# 3_RFID.net
KiCad netlist of a schematic drawn in Altium Designer
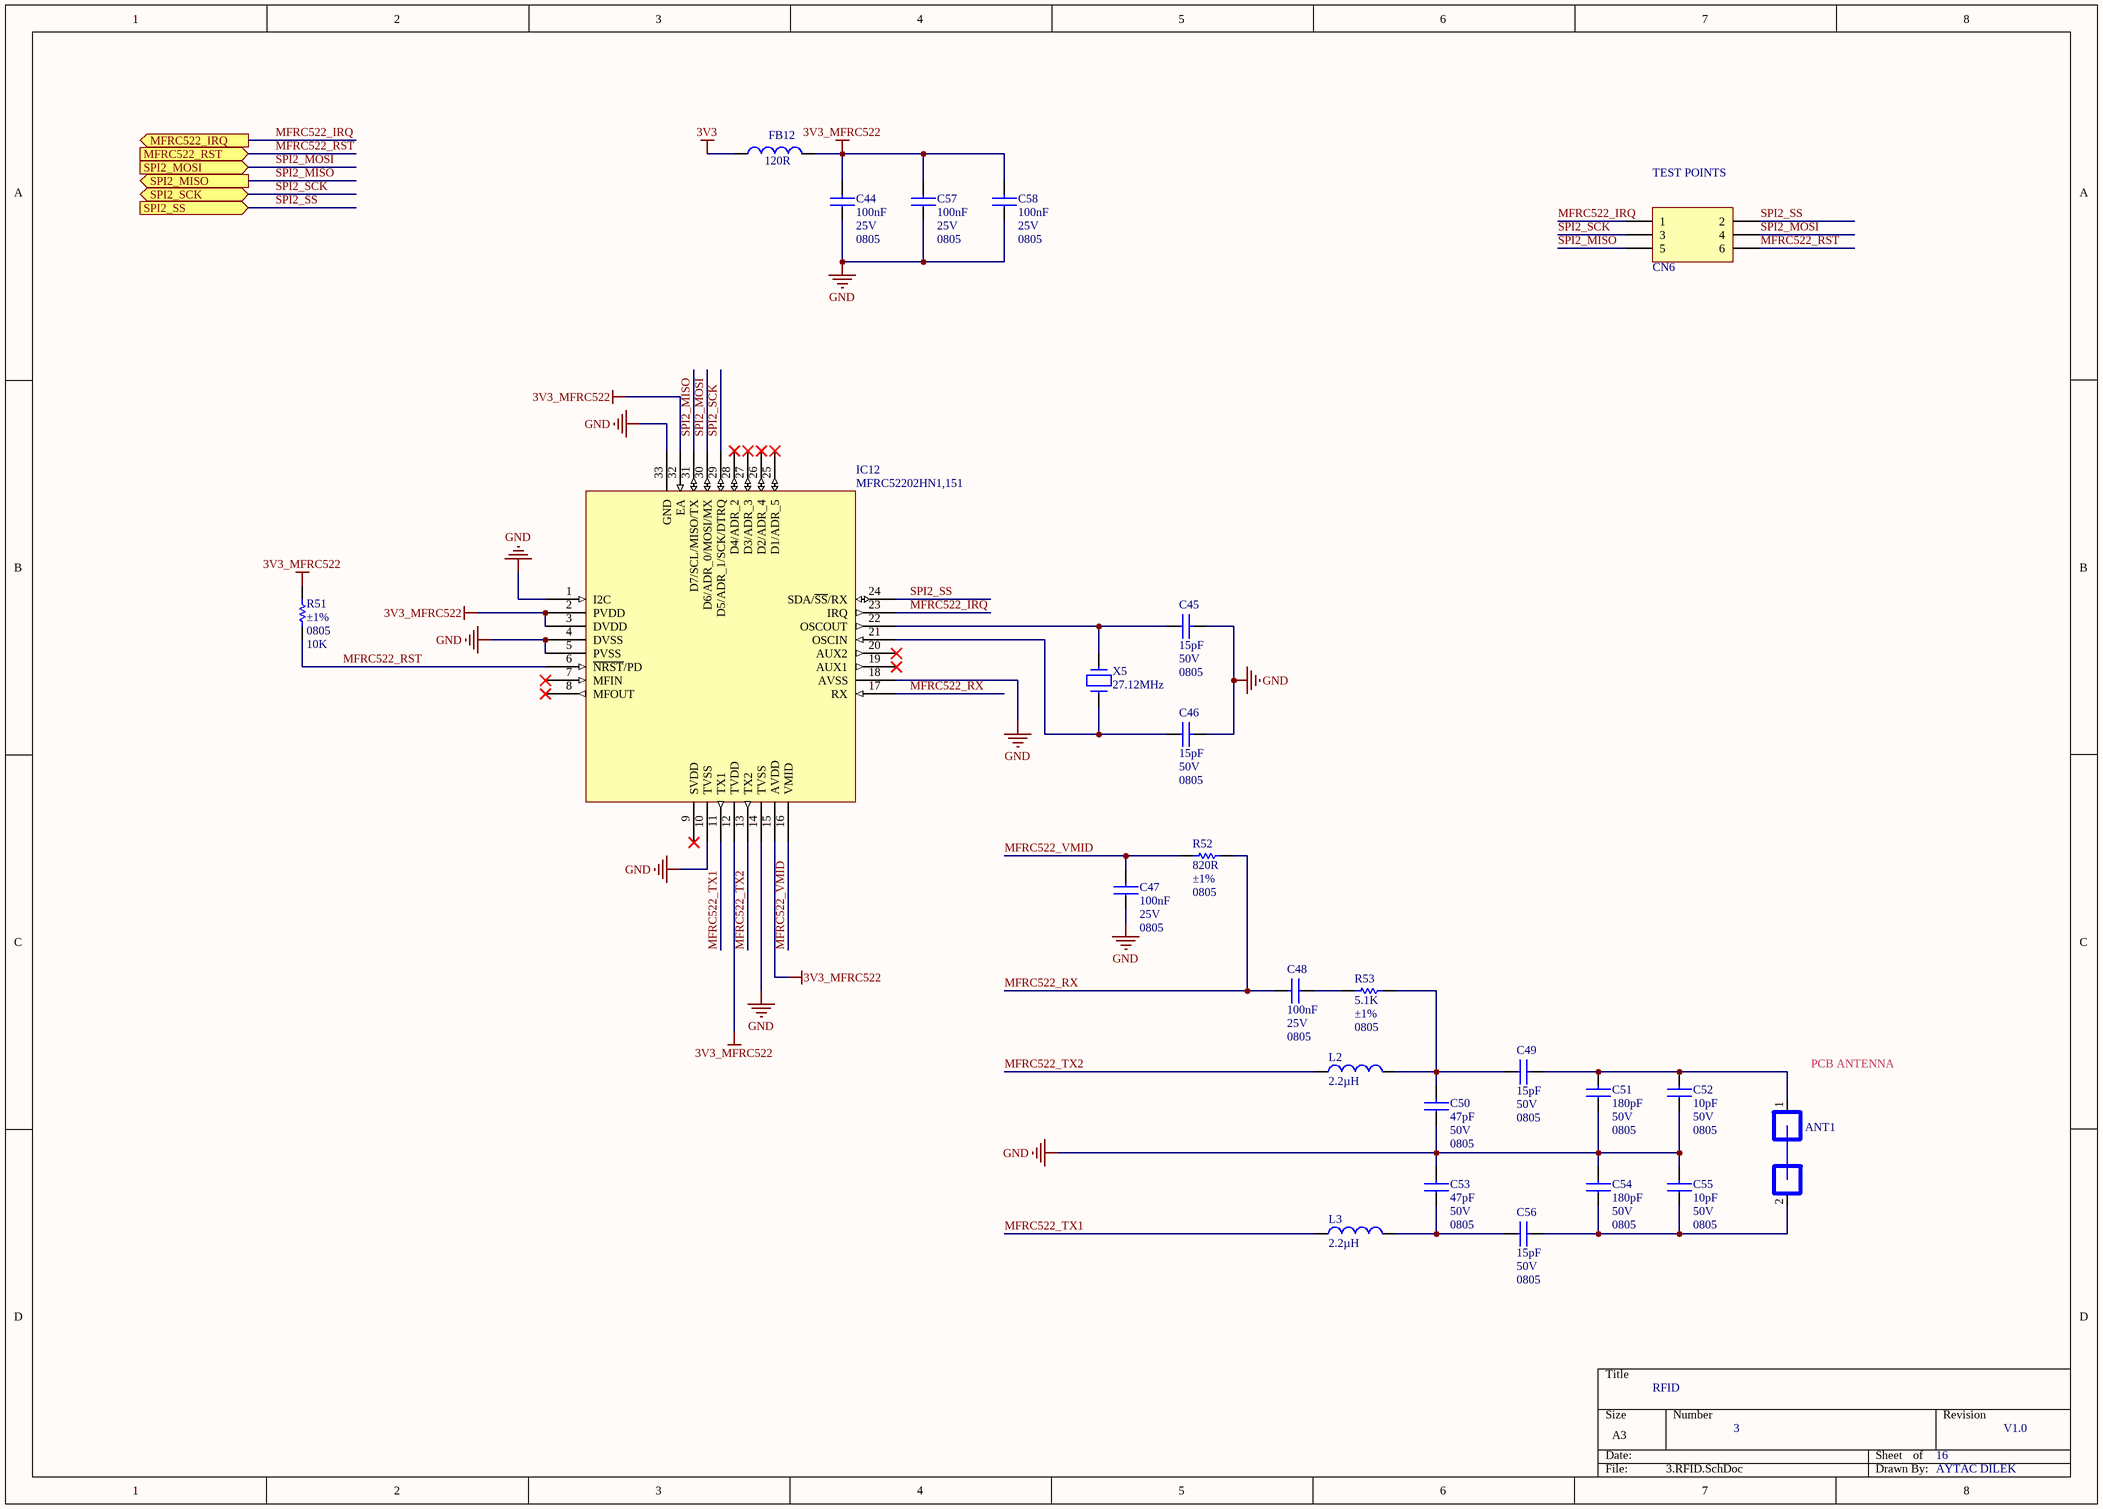
[diagram p0: 3.RFID.SchDoc]

(export (version "E")
  (design (tool "Eeschema 10.0.6"))
  (components
    (comp (ref "ANT1")
      (value "COIL_ANTENNA_PAD")
      (footprint "COIL_ANTENNA_PAD")
      (description "Coil Antenna Pad")
      (fields (field (name "PART NUMBER") "SMSC00008"))
      (libsource (lib "ComponentDatabase") (part "COIL_ANTENNA_PAD"))
    )
    (comp (ref "C44")
      (value "CAP_NP")
      (footprint "CAPC2012X100N_EIA0805")
      (description "CAP CER 0.1UF 25V X7R 0805")
      (fields
        (field (name "PART NUMBER") "SCAP00300093")
        (field (name "CAPACITANCE") "100nF")
        (field (name "TOLERANCE") "±10%")
        (field (name "VOLTAGE - RATED") "25V")
        (field (name "PACKAGE / CASE") "0805")
      )
      (libsource (lib "ComponentDatabase") (part "CAP_NP"))
    )
    (comp (ref "C45")
      (value "CAP_NP")
      (footprint "CAPC2012X100N_EIA0805")
      (description "CAP CER 15PF 50V NP0 0805")
      (fields
        (field (name "PART NUMBER") "SCAP00300038")
        (field (name "CAPACITANCE") "15pF")
        (field (name "TOLERANCE") "±5%")
        (field (name "VOLTAGE - RATED") "50V")
        (field (name "PACKAGE / CASE") "0805")
      )
      (libsource (lib "ComponentDatabase") (part "CAP_NP"))
    )
    (comp (ref "C46")
      (value "CAP_NP")
      (footprint "CAPC2012X100N_EIA0805")
      (description "CAP CER 15PF 50V NP0 0805")
      (fields
        (field (name "PART NUMBER") "SCAP00300038")
        (field (name "CAPACITANCE") "15pF")
        (field (name "TOLERANCE") "±5%")
        (field (name "VOLTAGE - RATED") "50V")
        (field (name "PACKAGE / CASE") "0805")
      )
      (libsource (lib "ComponentDatabase") (part "CAP_NP"))
    )
    (comp (ref "C47")
      (value "CAP_NP")
      (footprint "CAPC2012X100N_EIA0805")
      (description "CAP CER 0.1UF 25V X7R 0805")
      (fields
        (field (name "PART NUMBER") "SCAP00300093")
        (field (name "CAPACITANCE") "100nF")
        (field (name "TOLERANCE") "±10%")
        (field (name "VOLTAGE - RATED") "25V")
        (field (name "PACKAGE / CASE") "0805")
      )
      (libsource (lib "ComponentDatabase") (part "CAP_NP"))
    )
    (comp (ref "C48")
      (value "CAP_NP")
      (footprint "CAPC2012X100N_EIA0805")
      (description "CAP CER 0.1UF 25V X7R 0805")
      (fields
        (field (name "PART NUMBER") "SCAP00300093")
        (field (name "CAPACITANCE") "100nF")
        (field (name "TOLERANCE") "±10%")
        (field (name "VOLTAGE - RATED") "25V")
        (field (name "PACKAGE / CASE") "0805")
      )
      (libsource (lib "ComponentDatabase") (part "CAP_NP"))
    )
    (comp (ref "C49")
      (value "CAP_NP")
      (footprint "CAPC2012X100N_EIA0805")
      (description "CAP CER 15PF 50V NP0 0805")
      (fields
        (field (name "PART NUMBER") "SCAP00300038")
        (field (name "CAPACITANCE") "15pF")
        (field (name "TOLERANCE") "±5%")
        (field (name "VOLTAGE - RATED") "50V")
        (field (name "PACKAGE / CASE") "0805")
      )
      (libsource (lib "ComponentDatabase") (part "CAP_NP"))
    )
    (comp (ref "C50")
      (value "CAP_NP")
      (footprint "CAPC2012X100N_EIA0805")
      (description "CAP CER 47PF 50V NP0 0805")
      (fields
        (field (name "PART NUMBER") "SCAP00300050")
        (field (name "CAPACITANCE") "47pF")
        (field (name "TOLERANCE") "±5%")
        (field (name "VOLTAGE - RATED") "50V")
        (field (name "PACKAGE / CASE") "0805")
      )
      (libsource (lib "ComponentDatabase") (part "CAP_NP"))
    )
    (comp (ref "C51")
      (value "CAP_NP")
      (footprint "CAPC2012X100N_EIA0805")
      (description "CAP CER 180PF 50V NP0 0805")
      (fields
        (field (name "PART NUMBER") "SCAP00300064")
        (field (name "CAPACITANCE") "180pF")
        (field (name "TOLERANCE") "±5%")
        (field (name "VOLTAGE - RATED") "50V")
        (field (name "PACKAGE / CASE") "0805")
      )
      (libsource (lib "ComponentDatabase") (part "CAP_NP"))
    )
    (comp (ref "C52")
      (value "CAP_NP")
      (footprint "CAPC2012X100N_EIA0805")
      (description "CAP CER 10PF 50V NP0 0805")
      (fields
        (field (name "PART NUMBER") "SCAP00300034")
        (field (name "CAPACITANCE") "10pF")
        (field (name "TOLERANCE") "±0.25pF")
        (field (name "VOLTAGE - RATED") "50V")
        (field (name "PACKAGE / CASE") "0805")
      )
      (libsource (lib "ComponentDatabase") (part "CAP_NP"))
    )
    (comp (ref "C53")
      (value "CAP_NP")
      (footprint "CAPC2012X100N_EIA0805")
      (description "CAP CER 47PF 50V NP0 0805")
      (fields
        (field (name "PART NUMBER") "SCAP00300050")
        (field (name "CAPACITANCE") "47pF")
        (field (name "TOLERANCE") "±5%")
        (field (name "VOLTAGE - RATED") "50V")
        (field (name "PACKAGE / CASE") "0805")
      )
      (libsource (lib "ComponentDatabase") (part "CAP_NP"))
    )
    (comp (ref "C54")
      (value "CAP_NP")
      (footprint "CAPC2012X100N_EIA0805")
      (description "CAP CER 180PF 50V NP0 0805")
      (fields
        (field (name "PART NUMBER") "SCAP00300064")
        (field (name "CAPACITANCE") "180pF")
        (field (name "TOLERANCE") "±5%")
        (field (name "VOLTAGE - RATED") "50V")
        (field (name "PACKAGE / CASE") "0805")
      )
      (libsource (lib "ComponentDatabase") (part "CAP_NP"))
    )
    (comp (ref "C55")
      (value "CAP_NP")
      (footprint "CAPC2012X100N_EIA0805")
      (description "CAP CER 10PF 50V NP0 0805")
      (fields
        (field (name "PART NUMBER") "SCAP00300034")
        (field (name "CAPACITANCE") "10pF")
        (field (name "TOLERANCE") "±0.25pF")
        (field (name "VOLTAGE - RATED") "50V")
        (field (name "PACKAGE / CASE") "0805")
      )
      (libsource (lib "ComponentDatabase") (part "CAP_NP"))
    )
    (comp (ref "C56")
      (value "CAP_NP")
      (footprint "CAPC2012X100N_EIA0805")
      (description "CAP CER 15PF 50V NP0 0805")
      (fields
        (field (name "PART NUMBER") "SCAP00300038")
        (field (name "CAPACITANCE") "15pF")
        (field (name "TOLERANCE") "±5%")
        (field (name "VOLTAGE - RATED") "50V")
        (field (name "PACKAGE / CASE") "0805")
      )
      (libsource (lib "ComponentDatabase") (part "CAP_NP"))
    )
    (comp (ref "C57")
      (value "CAP_NP")
      (footprint "CAPC2012X100N_EIA0805")
      (description "CAP CER 0.1UF 25V X7R 0805")
      (fields
        (field (name "PART NUMBER") "SCAP00300093")
        (field (name "CAPACITANCE") "100nF")
        (field (name "TOLERANCE") "±10%")
        (field (name "VOLTAGE - RATED") "25V")
        (field (name "PACKAGE / CASE") "0805")
      )
      (libsource (lib "ComponentDatabase") (part "CAP_NP"))
    )
    (comp (ref "C58")
      (value "CAP_NP")
      (footprint "CAPC2012X100N_EIA0805")
      (description "CAP CER 0.1UF 25V X7R 0805")
      (fields
        (field (name "PART NUMBER") "SCAP00300093")
        (field (name "CAPACITANCE") "100nF")
        (field (name "TOLERANCE") "±10%")
        (field (name "VOLTAGE - RATED") "25V")
        (field (name "PACKAGE / CASE") "0805")
      )
      (libsource (lib "ComponentDatabase") (part "CAP_NP"))
    )
    (comp (ref "CN6")
      (value "HDR_2X3")
      (footprint "HDRV6W64P254_2X3_762X508X600P")
      (description "CONN HEADER FMALE 6PS .1\" DL TIN")
      (fields
        (field (name "PART NUMBER") "SCON00128")
        (field (name "MANUFACTURER") "Sullins Connector Solutions")
      )
      (libsource (lib "ComponentDatabase") (part "HDR_2X3"))
    )
    (comp (ref "FB12")
      (value "BEAD")
      (footprint "FILC2012X100N_EIA0805")
      (description "FERRITE CHIP POWER 120 OHM SMD")
      (fields
        (field (name "PART NUMBER") "SFIL00005")
        (field (name "IMPEDANCE") "120R")
        (field (name "MANUFACTURER") "Laird-Signal Integrity Products")
      )
      (libsource (lib "ComponentDatabase") (part "BEAD"))
    )
    (comp (ref "IC12")
      (value "MFRC522")
      (footprint "QFN50P500X500X100_HS-33N_[NXP]SOT617-1")
      (description "IC READER 13.56MHZ 32-HVQFN")
      (fields
        (field (name "PART NUMBER") "SRF000006")
        (field (name "MANUFACTURER") "NXP Semiconductors")
        (field (name "MANUFACTURER PART NUMBER") "MFRC52202HN1,151")
      )
      (libsource (lib "ComponentDatabase") (part "MFRC522"))
    )
    (comp (ref "L2")
      (value "INDUCTOR")
      (footprint "INDC2115X13N_EIA0805")
      (description "FIXED IND 2.2UH 1.3A 80 MOHM SMD")
      (fields
        (field (name "PART NUMBER") "SIND00007")
        (field (name "TOLERANCE") "±20%")
        (field (name "INDUCTANCE") "2.2µH")
      )
      (libsource (lib "ComponentDatabase") (part "INDUCTOR"))
    )
    (comp (ref "L3")
      (value "INDUCTOR")
      (footprint "INDC2115X13N_EIA0805")
      (description "FIXED IND 2.2UH 1.3A 80 MOHM SMD")
      (fields
        (field (name "PART NUMBER") "SIND00007")
        (field (name "TOLERANCE") "±20%")
        (field (name "INDUCTANCE") "2.2µH")
      )
      (libsource (lib "ComponentDatabase") (part "INDUCTOR"))
    )
    (comp (ref "R51")
      (value "RES")
      (footprint "RESC2013X65N_EIA0805")
      (description "RES SMD 10K OHM 1% 1/8W 0805")
      (fields
        (field (name "PART NUMBER") "SRES03010098")
        (field (name "TOLERANCE") "±1%")
        (field (name "PACKAGE / CASE") "0805")
        (field (name "RESISTANCE (OHM)") "10K")
        (field (name "MANUFACTURER") "Yageo")
      )
      (libsource (lib "ComponentDatabase") (part "RES"))
    )
    (comp (ref "R52")
      (value "820R")
      (footprint "RESC2013X65N_EIA0805")
      (description "RES SMD 820 OHM 1% 1/8W 0805")
      (fields
        (field (name "PART NUMBER") "SRES03010072")
        (field (name "TOLERANCE") "±1%")
        (field (name "PACKAGE / CASE") "0805")
        (field (name "MANUFACTURER") "Yageo")
      )
      (libsource (lib "ComponentDatabase") (part "RES"))
    )
    (comp (ref "R53")
      (value "5.1K")
      (footprint "RESC2013X65N_EIA0805")
      (description "RES SMD 5.1K OHM 1% 1/8W 0805")
      (fields
        (field (name "PART NUMBER") "SRES03010091")
        (field (name "TOLERANCE") "±1%")
        (field (name "PACKAGE / CASE") "0805")
        (field (name "MANUFACTURER") "Yageo")
      )
      (libsource (lib "ComponentDatabase") (part "RES"))
    )
    (comp (ref "X5")
      (value "27.12MHz")
      (footprint "HC-49/US")
      (description "CRYSTAL 27.1200MHZ 18PF SMD")
      (fields (field (name "PART NUMBER") "SCRY00017") (field (name "MANUFACTURER") "IQD"))
      (libsource (lib "ComponentDatabase") (part "CRYSTAL"))
    )
  )
  (nets
    (net (code "1") (name "/MFRC522_IRQ") (class "Default")
      (node (ref "CN6") (pin "1") (pinfunction "1_1") (pintype "passive"))
      (node (ref "IC12") (pin "23") (pinfunction "IRQ_23") (pintype "output"))
    )
    (net (code "2") (name "/MFRC522_RST") (class "Default")
      (node (ref "CN6") (pin "6") (pinfunction "6_6") (pintype "passive"))
      (node (ref "IC12") (pin "6") (pinfunction "~{NRST}/PD_6") (pintype "input"))
      (node (ref "R51") (pin "2") (pinfunction "2_2") (pintype "passive"))
    )
    (net (code "3") (name "/MFRC522_RX") (class "Default")
      (node (ref "C48") (pin "2") (pinfunction "2_2") (pintype "passive"))
      (node (ref "IC12") (pin "17") (pinfunction "RX_17") (pintype "input"))
      (node (ref "R52") (pin "1") (pinfunction "1_1") (pintype "passive"))
    )
    (net (code "4") (name "/MFRC522_TX1") (class "Default")
      (node (ref "IC12") (pin "11") (pinfunction "TX1_11") (pintype "output"))
      (node (ref "L3") (pin "1") (pinfunction "1_1") (pintype "passive"))
    )
    (net (code "5") (name "/MFRC522_TX2") (class "Default")
      (node (ref "IC12") (pin "13") (pinfunction "TX2_13") (pintype "output"))
      (node (ref "L2") (pin "1") (pinfunction "1_1") (pintype "passive"))
    )
    (net (code "6") (name "/MFRC522_VMID") (class "Default")
      (node (ref "C47") (pin "2") (pinfunction "2_2") (pintype "passive"))
      (node (ref "IC12") (pin "16") (pinfunction "VMID_16") (pintype "power_in"))
      (node (ref "R52") (pin "2") (pinfunction "2_2") (pintype "passive"))
    )
    (net (code "7") (name "/SPI2_MISO") (class "Default")
      (node (ref "CN6") (pin "5") (pinfunction "5_5") (pintype "passive"))
      (node (ref "IC12") (pin "31") (pinfunction "D7/SCL/MISO/TX_31") (pintype "bidirectional"))
    )
    (net (code "8") (name "/SPI2_MOSI") (class "Default")
      (node (ref "CN6") (pin "4") (pinfunction "4_4") (pintype "passive"))
      (node (ref "IC12") (pin "30") (pinfunction "D6/ADR_0/MOSI/MX_30") (pintype "bidirectional"))
    )
    (net (code "9") (name "/SPI2_SCK") (class "Default")
      (node (ref "CN6") (pin "3") (pinfunction "3_3") (pintype "passive"))
      (node (ref "IC12") (pin "29") (pinfunction "D5/ADR_1/SCK/DTRQ_29") (pintype "bidirectional"))
    )
    (net (code "10") (name "/SPI2_SS") (class "Default")
      (node (ref "CN6") (pin "2") (pinfunction "2_2") (pintype "passive"))
      (node (ref "IC12") (pin "24") (pinfunction "SDA/~{SS}/RX_24") (pintype "bidirectional"))
    )
    (net (code "11") (name "3V3") (class "Default")
      (node (ref "FB12") (pin "1") (pinfunction "1_1") (pintype "passive"))
    )
    (net (code "12") (name "3V3_MFRC522") (class "Default")
      (node (ref "C44") (pin "2") (pinfunction "2_2") (pintype "passive"))
      (node (ref "C57") (pin "2") (pinfunction "2_2") (pintype "passive"))
      (node (ref "C58") (pin "2") (pinfunction "2_2") (pintype "passive"))
      (node (ref "FB12") (pin "2") (pinfunction "2_2") (pintype "passive"))
      (node (ref "IC12") (pin "12") (pinfunction "TVDD_12") (pintype "power_in"))
      (node (ref "IC12") (pin "15") (pinfunction "AVDD_15") (pintype "power_in"))
      (node (ref "IC12") (pin "2") (pinfunction "PVDD_2") (pintype "power_in"))
      (node (ref "IC12") (pin "3") (pinfunction "DVDD_3") (pintype "power_in"))
      (node (ref "IC12") (pin "32") (pinfunction "EA_32") (pintype "input"))
      (node (ref "R51") (pin "1") (pinfunction "1_1") (pintype "passive"))
    )
    (net (code "13") (name "GND") (class "Default")
      (node (ref "C44") (pin "1") (pinfunction "1_1") (pintype "passive"))
      (node (ref "C45") (pin "2") (pinfunction "2_2") (pintype "passive"))
      (node (ref "C46") (pin "2") (pinfunction "2_2") (pintype "passive"))
      (node (ref "C47") (pin "1") (pinfunction "1_1") (pintype "passive"))
      (node (ref "C50") (pin "1") (pinfunction "1_1") (pintype "passive"))
      (node (ref "C51") (pin "1") (pinfunction "1_1") (pintype "passive"))
      (node (ref "C52") (pin "1") (pinfunction "1_1") (pintype "passive"))
      (node (ref "C53") (pin "2") (pinfunction "2_2") (pintype "passive"))
      (node (ref "C54") (pin "2") (pinfunction "2_2") (pintype "passive"))
      (node (ref "C55") (pin "2") (pinfunction "2_2") (pintype "passive"))
      (node (ref "C57") (pin "1") (pinfunction "1_1") (pintype "passive"))
      (node (ref "C58") (pin "1") (pinfunction "1_1") (pintype "passive"))
      (node (ref "IC12") (pin "1") (pinfunction "I2C_1") (pintype "input"))
      (node (ref "IC12") (pin "10") (pinfunction "TVSS_10") (pintype "power_in"))
      (node (ref "IC12") (pin "14") (pinfunction "TVSS_14") (pintype "power_in"))
      (node (ref "IC12") (pin "18") (pinfunction "AVSS_18") (pintype "power_in"))
      (node (ref "IC12") (pin "33") (pinfunction "GND_33") (pintype "power_in"))
      (node (ref "IC12") (pin "4") (pinfunction "DVSS_4") (pintype "power_in"))
      (node (ref "IC12") (pin "5") (pinfunction "PVSS_5") (pintype "power_in"))
    )
    (net (code "14") (name "Net-(ANT1-Pad1)") (class "Default")
      (node (ref "ANT1") (pin "1") (pinfunction "1_1") (pintype "passive"))
      (node (ref "C49") (pin "2") (pinfunction "2_2") (pintype "passive"))
      (node (ref "C51") (pin "2") (pinfunction "2_2") (pintype "passive"))
      (node (ref "C52") (pin "2") (pinfunction "2_2") (pintype "passive"))
    )
    (net (code "15") (name "Net-(ANT1-Pad2)") (class "Default")
      (node (ref "ANT1") (pin "2") (pinfunction "2_2") (pintype "passive"))
      (node (ref "C54") (pin "1") (pinfunction "1_1") (pintype "passive"))
      (node (ref "C55") (pin "1") (pinfunction "1_1") (pintype "passive"))
      (node (ref "C56") (pin "2") (pinfunction "2_2") (pintype "passive"))
    )
    (net (code "16") (name "Net-(C48-Pad1)") (class "Default")
      (node (ref "C48") (pin "1") (pinfunction "1_1") (pintype "passive"))
      (node (ref "R53") (pin "2") (pinfunction "2_2") (pintype "passive"))
    )
    (net (code "17") (name "Net-(C49-Pad1)") (class "Default")
      (node (ref "C49") (pin "1") (pinfunction "1_1") (pintype "passive"))
      (node (ref "C50") (pin "2") (pinfunction "2_2") (pintype "passive"))
      (node (ref "L2") (pin "2") (pinfunction "2_2") (pintype "passive"))
      (node (ref "R53") (pin "1") (pinfunction "1_1") (pintype "passive"))
    )
    (net (code "18") (name "Net-(C53-Pad1)") (class "Default")
      (node (ref "C53") (pin "1") (pinfunction "1_1") (pintype "passive"))
      (node (ref "C56") (pin "1") (pinfunction "1_1") (pintype "passive"))
      (node (ref "L3") (pin "2") (pinfunction "2_2") (pintype "passive"))
    )
    (net (code "19") (name "Net-(IC12-OSCIN)") (class "Default")
      (node (ref "C46") (pin "1") (pinfunction "1_1") (pintype "passive"))
      (node (ref "IC12") (pin "21") (pinfunction "OSCIN_21") (pintype "input"))
      (node (ref "X5") (pin "2") (pinfunction "2_2") (pintype "passive"))
    )
    (net (code "20") (name "Net-(IC12-OSCOUT)") (class "Default")
      (node (ref "C45") (pin "1") (pinfunction "1_1") (pintype "passive"))
      (node (ref "IC12") (pin "22") (pinfunction "OSCOUT_22") (pintype "output"))
      (node (ref "X5") (pin "1") (pinfunction "1_1") (pintype "passive"))
    )
    (net (code "21") (name "unconnected-(IC12-AUX1-Pad19)") (class "Default")
      (node (ref "IC12") (pin "19") (pinfunction "AUX1_19") (pintype "output+no_connect"))
    )
    (net (code "22") (name "unconnected-(IC12-AUX2-Pad20)") (class "Default")
      (node (ref "IC12") (pin "20") (pinfunction "AUX2_20") (pintype "output+no_connect"))
    )
    (net (code "23") (name "unconnected-(IC12-D1{slash}ADR_5-Pad25)") (class "Default")
      (node (ref "IC12") (pin "25") (pinfunction "D1/ADR_5_25") (pintype "bidirectional+no_connect"))
    )
    (net (code "24") (name "unconnected-(IC12-D2{slash}ADR_4-Pad26)") (class "Default")
      (node (ref "IC12") (pin "26") (pinfunction "D2/ADR_4_26") (pintype "bidirectional+no_connect"))
    )
    (net (code "25") (name "unconnected-(IC12-D3{slash}ADR_3-Pad27)") (class "Default")
      (node (ref "IC12") (pin "27") (pinfunction "D3/ADR_3_27") (pintype "bidirectional+no_connect"))
    )
    (net (code "26") (name "unconnected-(IC12-D4{slash}ADR_2-Pad28)") (class "Default")
      (node (ref "IC12") (pin "28") (pinfunction "D4/ADR_2_28") (pintype "bidirectional+no_connect"))
    )
    (net (code "27") (name "unconnected-(IC12-MFIN-Pad7)") (class "Default")
      (node (ref "IC12") (pin "7") (pinfunction "MFIN_7") (pintype "input+no_connect"))
    )
    (net (code "28") (name "unconnected-(IC12-MFOUT-Pad8)") (class "Default")
      (node (ref "IC12") (pin "8") (pinfunction "MFOUT_8") (pintype "output+no_connect"))
    )
    (net (code "29") (name "unconnected-(IC12-SVDD-Pad9)") (class "Default")
      (node (ref "IC12") (pin "9") (pinfunction "SVDD_9") (pintype "power_in+no_connect"))
    )
  )
)
